# current_monitor_v1-1.net
KiCad netlist of a schematic drawn in EAGLE
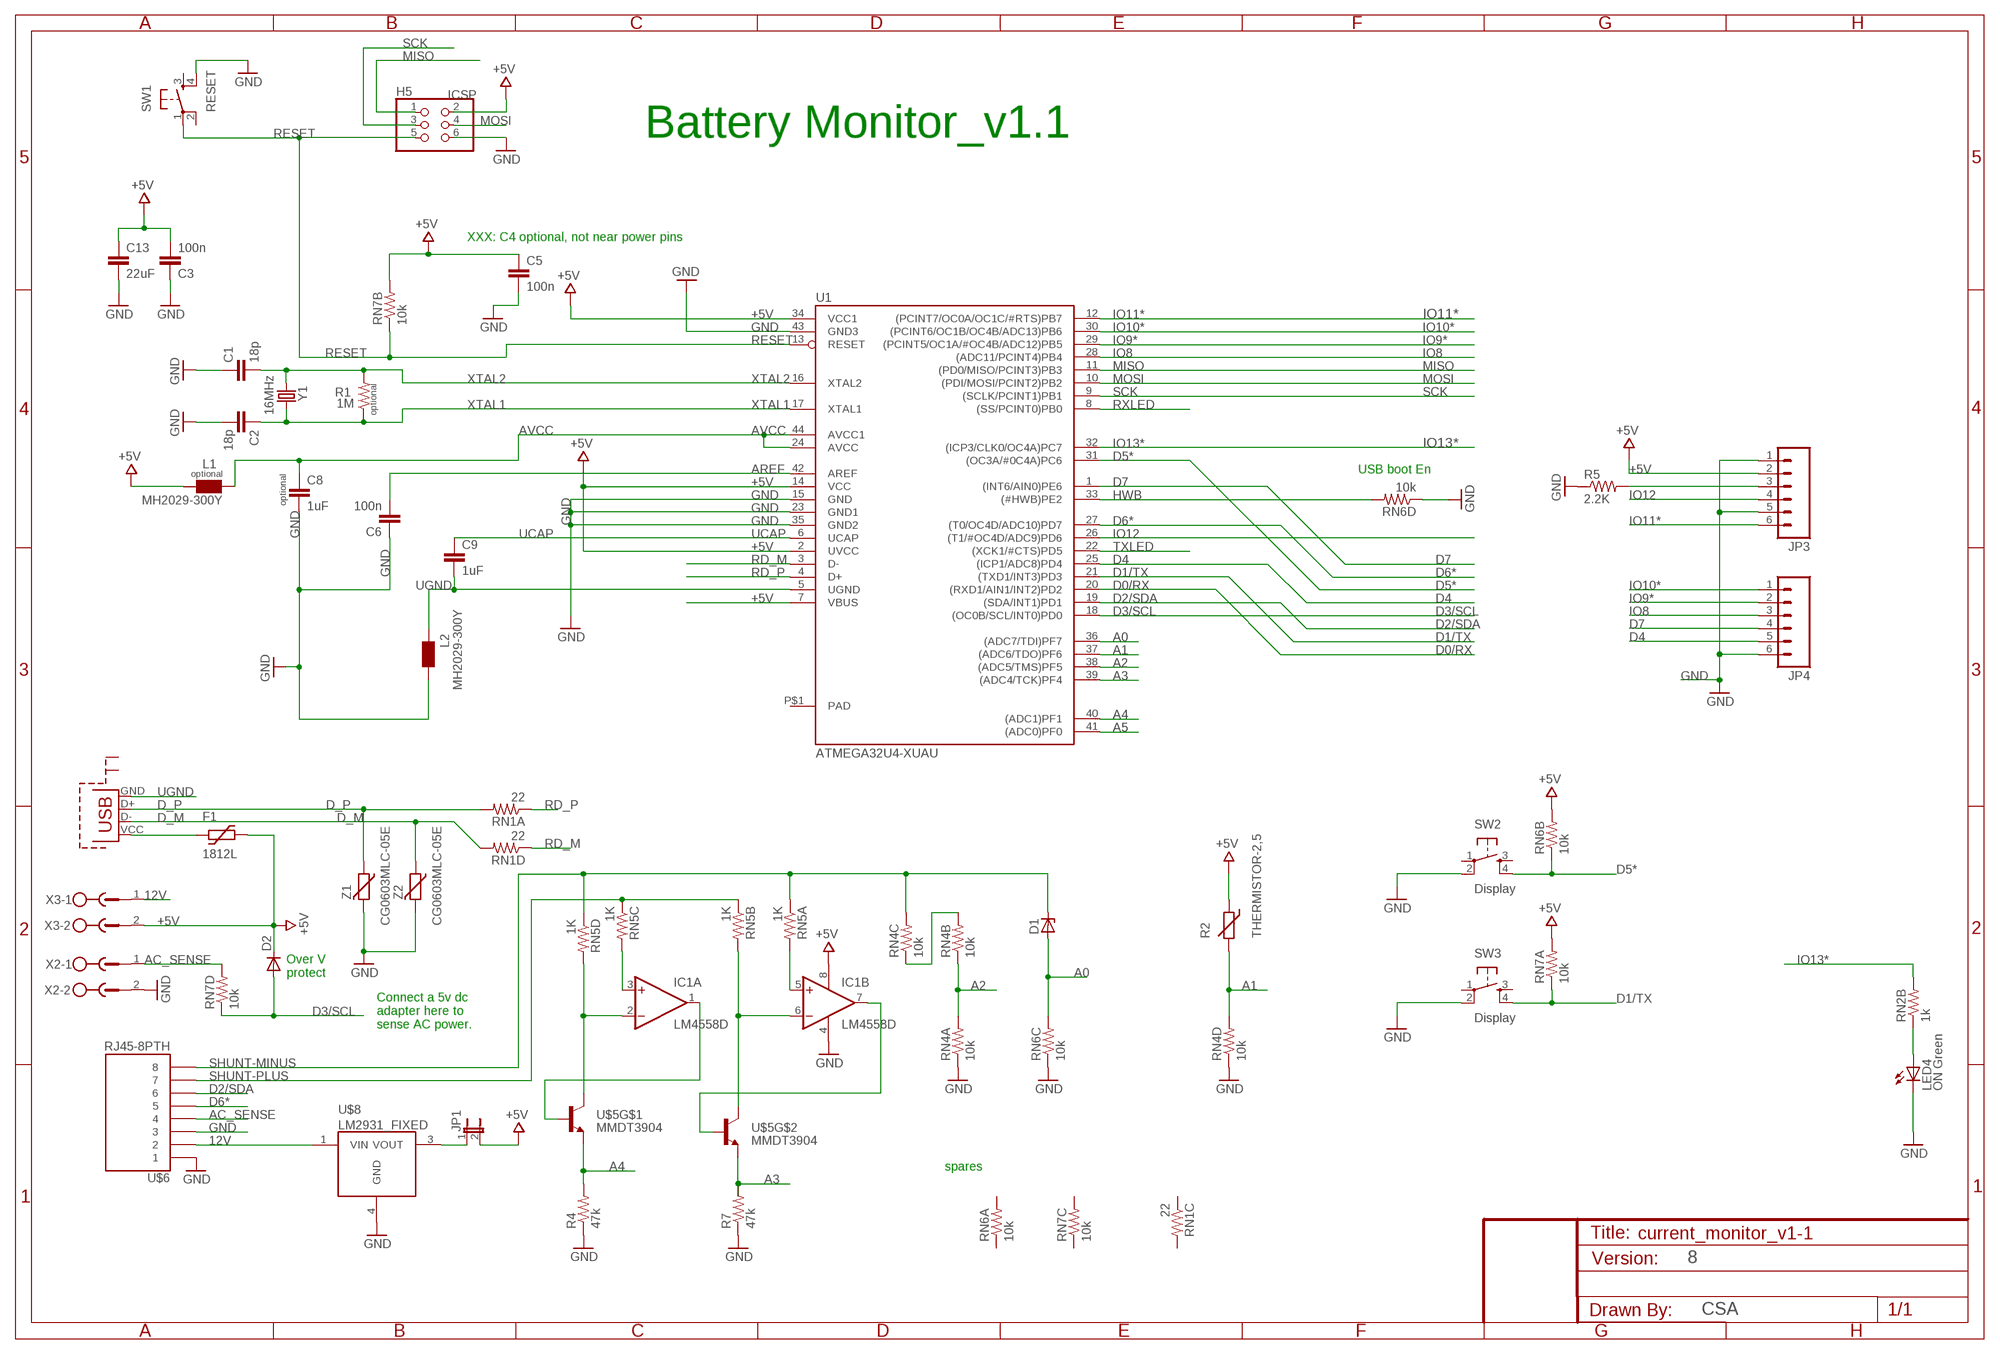
[diagram p0: schematic, sheet 1]

(export (version "E")
  (design (tool "Eeschema 10.0.6"))
  (components
    (comp (ref "C1")
      (value "18p")
      (footprint "eagle-import:0805")
      (libsource (lib "eagle-import") (part "CAP0805"))
    )
    (comp (ref "C2")
      (value "18p")
      (footprint "eagle-import:0805")
      (libsource (lib "eagle-import") (part "CAP0805"))
    )
    (comp (ref "C3")
      (value "100n")
      (footprint "eagle-import:0805")
      (libsource (lib "eagle-import") (part "CAP0805"))
    )
    (comp (ref "C5")
      (value "100n")
      (footprint "eagle-import:0805")
      (libsource (lib "eagle-import") (part "CAP0805"))
    )
    (comp (ref "C6")
      (value "100n")
      (footprint "eagle-import:0805")
      (libsource (lib "eagle-import") (part "CAP0805"))
    )
    (comp (ref "C8")
      (value "1uF")
      (footprint "eagle-import:0805")
      (libsource (lib "eagle-import") (part "CAP0805"))
    )
    (comp (ref "C9")
      (value "1uF")
      (footprint "eagle-import:0805")
      (libsource (lib "eagle-import") (part "CAP0805"))
    )
    (comp (ref "C13")
      (value "22uF")
      (footprint "eagle-import:1206")
      (libsource (lib "eagle-import") (part "CAP1206"))
    )
    (comp (ref "D1")
      (value "ZENER-DIODEZD-5")
      (footprint "eagle-import:ZDIO-5")
      (libsource (lib "eagle-import") (part "ZENER-DIODEZD-5"))
    )
    (comp (ref "D2")
      (value "DIODESMA")
      (footprint "eagle-import:SMA-DIODE")
      (libsource (lib "eagle-import") (part "DIODESMA"))
    )
    (comp (ref "F1")
      (value "1812L")
      (footprint "eagle-import:1812L")
      (libsource (lib "eagle-import") (part "1812L"))
    )
    (comp (ref "H5")
      (value "ICSP")
      (footprint "eagle-import:2X03")
      (libsource (lib "eagle-import") (part "PINHD-2X3"))
    )
    (comp (ref "IC1")
      (value "LM4558D")
      (footprint "eagle-import:SO08")
      (libsource (lib "eagle-import") (part "4558DLM"))
    )
    (comp (ref "JP1")
      (value "JUMPER-2-OLDPTH_LOCK")
      (footprint "eagle-import:1X02_LOCK")
      (libsource (lib "eagle-import") (part "JUMPER-2-OLDPTH_LOCK"))
    )
    (comp (ref "JP3")
      (value "M06FEMALE_LOCK")
      (footprint "eagle-import:1X06_FEMALE_LOCK.010")
      (libsource (lib "eagle-import") (part "M06FEMALE_LOCK"))
    )
    (comp (ref "JP4")
      (value "M06FEMALE_LOCK")
      (footprint "eagle-import:1X06_FEMALE_LOCK.010")
      (libsource (lib "eagle-import") (part "M06FEMALE_LOCK"))
    )
    (comp (ref "L1")
      (value "MH2029-300Y")
      (footprint "eagle-import:0805")
      (libsource (lib "eagle-import") (part "WE-CBF_0805"))
    )
    (comp (ref "L2")
      (value "MH2029-300Y")
      (footprint "eagle-import:0805")
      (libsource (lib "eagle-import") (part "WE-CBF_0805"))
    )
    (comp (ref "LED4")
      (value "ON Green")
      (footprint "eagle-import:LED0805")
      (libsource (lib "eagle-import") (part "LED0805"))
    )
    (comp (ref "R1")
      (value "1M")
      (footprint "eagle-import:0805")
      (libsource (lib "eagle-import") (part "RESISTOR0805-RES"))
    )
    (comp (ref "R2")
      (value "THERMISTOR-2,5")
      (footprint "eagle-import:RS-2,5")
      (libsource (lib "eagle-import") (part "THERMISTOR-2,5"))
    )
    (comp (ref "R4")
      (value "47k")
      (footprint "eagle-import:0805")
      (libsource (lib "eagle-import") (part "RESISTOR0805-RES"))
    )
    (comp (ref "R5")
      (value "2.2K")
      (footprint "eagle-import:0805")
      (libsource (lib "eagle-import") (part "RESISTOR0805-RES"))
    )
    (comp (ref "R7")
      (value "47k")
      (footprint "eagle-import:0805")
      (libsource (lib "eagle-import") (part "RESISTOR0805-RES"))
    )
    (comp (ref "RN1")
      (value "22")
      (footprint "eagle-import:CRA06S")
      (libsource (lib "eagle-import") (part "RESISTOR-ARRAYCRA06S"))
    )
    (comp (ref "RN2")
      (value "1k")
      (footprint "eagle-import:CRA06S")
      (libsource (lib "eagle-import") (part "RESISTOR-ARRAYCRA06S"))
    )
    (comp (ref "RN4")
      (value "10k")
      (footprint "eagle-import:CRA06S")
      (libsource (lib "eagle-import") (part "RESISTOR-ARRAYCRA06S"))
    )
    (comp (ref "RN5")
      (value "1K")
      (footprint "eagle-import:CRA06S")
      (libsource (lib "eagle-import") (part "RESISTOR-ARRAYCRA06S"))
    )
    (comp (ref "RN6")
      (value "10k")
      (footprint "eagle-import:CRA06S")
      (libsource (lib "eagle-import") (part "RESISTOR-ARRAYCRA06S"))
    )
    (comp (ref "RN7")
      (value "10k")
      (footprint "eagle-import:CRA06S")
      (libsource (lib "eagle-import") (part "RESISTOR-ARRAYCRA06S"))
    )
    (comp (ref "SW1")
      (value "RESET")
      (footprint "eagle-import:TACTILE-PTH")
      (libsource (lib "eagle-import") (part "TAC_SWITCHPTH"))
    )
    (comp (ref "SW2")
      (value "Display")
      (footprint "eagle-import:TACTILE-PTH")
      (libsource (lib "eagle-import") (part "TAC_SWITCHPTH"))
    )
    (comp (ref "SW3")
      (value "Display")
      (footprint "eagle-import:TACTILE-PTH")
      (libsource (lib "eagle-import") (part "TAC_SWITCHPTH"))
    )
    (comp (ref "U$5")
      (value "MMDT3904")
      (footprint "eagle-import:SOT363")
      (libsource (lib "eagle-import") (part "MMDT3904"))
    )
    (comp (ref "U$6")
      (value "RJ45-8PTH")
      (footprint "eagle-import:RJ45-8")
      (libsource (lib "eagle-import") (part "RJ45-8PTH"))
    )
    (comp (ref "U$8")
      (value "LM2931_FIXED")
      (footprint "eagle-import:DPAK")
      (libsource (lib "eagle-import") (part "LM2931_FIXED"))
    )
    (comp (ref "U$12")
      (value "USB-MICRO-B-EVT")
      (footprint "eagle-import:USB-MICRO-B-UNIVERSAL-SOLID-FOOTS")
      (libsource (lib "eagle-import") (part "USB-MICRO-B-EVT"))
    )
    (comp (ref "U1")
      (value "ATMEGA32U4-XUAU")
      (footprint "eagle-import:TQFP44-PAD")
      (libsource (lib "eagle-import") (part "ATMEGA32U4-XUAU"))
    )
    (comp (ref "X2")
      (value "MSTBV2")
      (footprint "eagle-import:MSTBV2")
      (libsource (lib "eagle-import") (part "MSTBV2"))
    )
    (comp (ref "X3")
      (value "MSTBV2")
      (footprint "eagle-import:MSTBV2")
      (libsource (lib "eagle-import") (part "MSTBV2"))
    )
    (comp (ref "Y1")
      (value "16MHz")
      (footprint "eagle-import:HC49US")
      (libsource (lib "eagle-import") (part "CRYSTALHC49US"))
    )
    (comp (ref "Z1")
      (value "CG0603MLC-05E")
      (footprint "eagle-import:CT_CN0603")
      (libsource (lib "eagle-import") (part "VARISTORCN0603"))
    )
    (comp (ref "Z2")
      (value "CG0603MLC-05E")
      (footprint "eagle-import:CT_CN0603")
      (libsource (lib "eagle-import") (part "VARISTORCN0603"))
    )
  )
  (nets
    (net (code "1") (name "+5V") (class "Default")
      (node (ref "C13") (pin "1") (pinfunction "1_1") (pintype "passive"))
      (node (ref "C3") (pin "2") (pinfunction "2_2") (pintype "passive"))
      (node (ref "C5") (pin "1") (pinfunction "1_1") (pintype "passive"))
      (node (ref "D2") (pin "C") (pinfunction "C_C") (pintype "passive"))
      (node (ref "F1") (pin "P$2") (pinfunction "2_P$2") (pintype "passive"))
      (node (ref "H5") (pin "2") (pinfunction "2_2") (pintype "passive"))
      (node (ref "IC1") (pin "8") (pinfunction "V+_8") (pintype "power_in"))
      (node (ref "JP1") (pin "2") (pinfunction "2_2") (pintype "passive"))
      (node (ref "JP3") (pin "2") (pinfunction "2_2") (pintype "passive"))
      (node (ref "L1") (pin "1") (pinfunction "1_1") (pintype "passive"))
      (node (ref "R2") (pin "1") (pinfunction "1_1") (pintype "passive"))
      (node (ref "RN6") (pin "7") (pinfunction "2_7") (pintype "passive"))
      (node (ref "RN7") (pin "7") (pinfunction "2_7") (pintype "passive"))
      (node (ref "RN7") (pin "8") (pinfunction "2_8") (pintype "passive"))
      (node (ref "U1") (pin "14") (pinfunction "VCC_14") (pintype "power_in"))
      (node (ref "U1") (pin "2") (pinfunction "UVCC_2") (pintype "power_in"))
      (node (ref "U1") (pin "34") (pinfunction "VCC1_34") (pintype "power_in"))
      (node (ref "U1") (pin "7") (pinfunction "VBUS_7") (pintype "input"))
      (node (ref "X3") (pin "2") (pinfunction "SK_2") (pintype "passive"))
    )
    (net (code "2") (name "/12V") (class "Default")
      (node (ref "U$6") (pin "2") (pinfunction "2_2") (pintype "bidirectional"))
      (node (ref "U$8") (pin "1") (pinfunction "VIN_1") (pintype "bidirectional"))
      (node (ref "X3") (pin "1") (pinfunction "SK_1") (pintype "passive"))
    )
    (net (code "3") (name "/A0") (class "Default")
      (node (ref "D1") (pin "A") (pinfunction "A_A") (pintype "passive"))
      (node (ref "RN6") (pin "6") (pinfunction "2_6") (pintype "passive"))
      (node (ref "U1") (pin "36") (pinfunction "(ADC7/TDI)PF7_36") (pintype "bidirectional"))
    )
    (net (code "4") (name "/A1") (class "Default")
      (node (ref "R2") (pin "2") (pinfunction "2_2") (pintype "passive"))
      (node (ref "RN4") (pin "5") (pinfunction "2_5") (pintype "passive"))
      (node (ref "U1") (pin "37") (pinfunction "(ADC6/TDO)PF6_37") (pintype "bidirectional"))
    )
    (net (code "5") (name "/A2") (class "Default")
      (node (ref "RN4") (pin "2") (pinfunction "1_2") (pintype "passive"))
      (node (ref "RN4") (pin "8") (pinfunction "2_8") (pintype "passive"))
      (node (ref "U1") (pin "38") (pinfunction "(ADC5/TMS)PF5_38") (pintype "bidirectional"))
    )
    (net (code "6") (name "/A3") (class "Default")
      (node (ref "R7") (pin "2") (pinfunction "2_2") (pintype "passive"))
      (node (ref "U$5") (pin "1") (pinfunction "E_1") (pintype "passive"))
      (node (ref "U1") (pin "39") (pinfunction "(ADC4/TCK)PF4_39") (pintype "bidirectional"))
    )
    (net (code "7") (name "/A4") (class "Default")
      (node (ref "R4") (pin "2") (pinfunction "2_2") (pintype "passive"))
      (node (ref "U$5") (pin "4") (pinfunction "E_4") (pintype "passive"))
      (node (ref "U1") (pin "40") (pinfunction "(ADC1)PF1_40") (pintype "bidirectional"))
    )
    (net (code "8") (name "/A5") (class "Default")
      (node (ref "U1") (pin "41") (pinfunction "(ADC0)PF0_41") (pintype "bidirectional"))
    )
    (net (code "9") (name "/AC_SENSE") (class "Default")
      (node (ref "RN7") (pin "5") (pinfunction "2_5") (pintype "passive"))
      (node (ref "U$6") (pin "4") (pinfunction "4_4") (pintype "bidirectional"))
      (node (ref "X2") (pin "1") (pinfunction "SK_1") (pintype "passive"))
    )
    (net (code "10") (name "/AREF") (class "Default")
      (node (ref "C6") (pin "2") (pinfunction "2_2") (pintype "passive"))
      (node (ref "U1") (pin "42") (pinfunction "AREF_42") (pintype "power_in"))
    )
    (net (code "11") (name "/AVCC") (class "Default")
      (node (ref "C8") (pin "1") (pinfunction "1_1") (pintype "passive"))
      (node (ref "L1") (pin "2") (pinfunction "2_2") (pintype "passive"))
      (node (ref "U1") (pin "24") (pinfunction "AVCC_24") (pintype "power_in"))
      (node (ref "U1") (pin "44") (pinfunction "AVCC1_44") (pintype "power_in"))
    )
    (net (code "12") (name "/D0{slash}RX") (class "Default")
      (node (ref "U1") (pin "20") (pinfunction "(RXD1/AIN1/INT2)PD2_20") (pintype "bidirectional"))
    )
    (net (code "13") (name "/D1{slash}TX") (class "Default")
      (node (ref "RN7") (pin "1") (pinfunction "1_1") (pintype "passive"))
      (node (ref "SW3") (pin "4") (pinfunction "4_4") (pintype "passive"))
      (node (ref "U1") (pin "21") (pinfunction "(TXD1/INT3)PD3_21") (pintype "bidirectional"))
    )
    (net (code "14") (name "/D2{slash}SDA") (class "Default")
      (node (ref "U$6") (pin "6") (pinfunction "6_6") (pintype "bidirectional"))
      (node (ref "U1") (pin "19") (pinfunction "(SDA/INT1)PD1_19") (pintype "bidirectional"))
    )
    (net (code "15") (name "/D3{slash}SCL") (class "Default")
      (node (ref "D2") (pin "A") (pinfunction "A_A") (pintype "passive"))
      (node (ref "RN7") (pin "4") (pinfunction "1_4") (pintype "passive"))
      (node (ref "U1") (pin "18") (pinfunction "(OC0B/SCL/INT0)PD0_18") (pintype "bidirectional"))
    )
    (net (code "16") (name "/D4") (class "Default")
      (node (ref "JP4") (pin "5") (pinfunction "5_5") (pintype "passive"))
      (node (ref "U1") (pin "25") (pinfunction "(ICP1/ADC8)PD4_25") (pintype "bidirectional"))
    )
    (net (code "17") (name "/D5*") (class "Default")
      (node (ref "RN6") (pin "2") (pinfunction "1_2") (pintype "passive"))
      (node (ref "SW2") (pin "4") (pinfunction "4_4") (pintype "passive"))
      (node (ref "U1") (pin "31") (pinfunction "(OC3A/#0C4A)PC6_31") (pintype "bidirectional"))
    )
    (net (code "18") (name "/D6*") (class "Default")
      (node (ref "U$6") (pin "5") (pinfunction "5_5") (pintype "bidirectional"))
      (node (ref "U1") (pin "27") (pinfunction "(T0/OC4D/ADC10)PD7_27") (pintype "bidirectional"))
    )
    (net (code "19") (name "/D7") (class "Default")
      (node (ref "JP4") (pin "4") (pinfunction "4_4") (pintype "passive"))
      (node (ref "U1") (pin "1") (pinfunction "(INT6/AIN0)PE6_1") (pintype "bidirectional"))
    )
    (net (code "20") (name "/D_M") (class "Default")
      (node (ref "RN1") (pin "5") (pinfunction "2_5") (pintype "passive"))
      (node (ref "U$12") (pin "D-") (pinfunction "D-_D-") (pintype "bidirectional"))
      (node (ref "Z2") (pin "1") (pinfunction "1_1") (pintype "passive"))
    )
    (net (code "21") (name "/D_P") (class "Default")
      (node (ref "RN1") (pin "8") (pinfunction "2_8") (pintype "passive"))
      (node (ref "U$12") (pin "D+") (pinfunction "D+_D+") (pintype "bidirectional"))
      (node (ref "Z1") (pin "1") (pinfunction "1_1") (pintype "passive"))
    )
    (net (code "22") (name "/HWB") (class "Default")
      (node (ref "RN6") (pin "5") (pinfunction "2_5") (pintype "passive"))
      (node (ref "U1") (pin "33") (pinfunction "(#HWB)PE2_33") (pintype "bidirectional"))
    )
    (net (code "23") (name "/IO8") (class "Default")
      (node (ref "JP4") (pin "3") (pinfunction "3_3") (pintype "passive"))
      (node (ref "U1") (pin "28") (pinfunction "(ADC11/PCINT4)PB4_28") (pintype "bidirectional"))
    )
    (net (code "24") (name "/IO9*") (class "Default")
      (node (ref "JP4") (pin "2") (pinfunction "2_2") (pintype "passive"))
      (node (ref "U1") (pin "29") (pinfunction "(PCINT5/OC1A/#OC4B/ADC12)PB5_29") (pintype "bidirectional"))
    )
    (net (code "25") (name "/IO10*") (class "Default")
      (node (ref "JP4") (pin "1") (pinfunction "1_1") (pintype "passive"))
      (node (ref "U1") (pin "30") (pinfunction "(PCINT6/OC1B/OC4B/ADC13)PB6_30") (pintype "bidirectional"))
    )
    (net (code "26") (name "/IO11*") (class "Default")
      (node (ref "JP3") (pin "6") (pinfunction "6_6") (pintype "passive"))
      (node (ref "U1") (pin "12") (pinfunction "(PCINT7/OC0A/OC1C/#RTS)PB7_12") (pintype "bidirectional"))
    )
    (net (code "27") (name "/IO12") (class "Default")
      (node (ref "JP3") (pin "4") (pinfunction "4_4") (pintype "passive"))
      (node (ref "U1") (pin "26") (pinfunction "(T1/#OC4D/ADC9)PD6_26") (pintype "bidirectional"))
    )
    (net (code "28") (name "/IO13*") (class "Default")
      (node (ref "RN2") (pin "7") (pinfunction "2_7") (pintype "passive"))
      (node (ref "U1") (pin "32") (pinfunction "(ICP3/CLK0/OC4A)PC7_32") (pintype "bidirectional"))
    )
    (net (code "29") (name "/MISO") (class "Default")
      (node (ref "H5") (pin "1") (pinfunction "1_1") (pintype "passive"))
      (node (ref "U1") (pin "11") (pinfunction "(PD0/MISO/PCINT3)PB3_11") (pintype "bidirectional"))
    )
    (net (code "30") (name "/MOSI") (class "Default")
      (node (ref "H5") (pin "4") (pinfunction "4_4") (pintype "passive"))
      (node (ref "U1") (pin "10") (pinfunction "(PDI/MOSI/PCINT2)PB2_10") (pintype "bidirectional"))
    )
    (net (code "31") (name "/PAD") (class "Default")
      (node (ref "U1") (pin "P$1") (pinfunction "PAD_P$1") (pintype "power_in"))
    )
    (net (code "32") (name "/RD_M") (class "Default")
      (node (ref "RN1") (pin "4") (pinfunction "1_4") (pintype "passive"))
      (node (ref "U1") (pin "3") (pinfunction "D-_3") (pintype "bidirectional"))
    )
    (net (code "33") (name "/RD_P") (class "Default")
      (node (ref "RN1") (pin "1") (pinfunction "1_1") (pintype "passive"))
      (node (ref "U1") (pin "4") (pinfunction "D+_4") (pintype "bidirectional"))
    )
    (net (code "34") (name "/RESET") (class "Default")
      (node (ref "H5") (pin "5") (pinfunction "5_5") (pintype "passive"))
      (node (ref "RN7") (pin "2") (pinfunction "1_2") (pintype "passive"))
      (node (ref "SW1") (pin "1") (pinfunction "1_1") (pintype "passive"))
      (node (ref "U1") (pin "13") (pinfunction "RESET_13") (pintype "input"))
    )
    (net (code "35") (name "/RXLED") (class "Default")
      (node (ref "U1") (pin "8") (pinfunction "(SS/PCINT0)PB0_8") (pintype "bidirectional"))
    )
    (net (code "36") (name "/SCK") (class "Default")
      (node (ref "H5") (pin "3") (pinfunction "3_3") (pintype "passive"))
      (node (ref "U1") (pin "9") (pinfunction "(SCLK/PCINT1)PB1_9") (pintype "bidirectional"))
    )
    (net (code "37") (name "/SHUNT-MINUS") (class "Default")
      (node (ref "D1") (pin "C") (pinfunction "C_C") (pintype "passive"))
      (node (ref "RN4") (pin "6") (pinfunction "2_6") (pintype "passive"))
      (node (ref "RN5") (pin "1") (pinfunction "1_1") (pintype "passive"))
      (node (ref "RN5") (pin "4") (pinfunction "1_4") (pintype "passive"))
      (node (ref "U$6") (pin "8") (pinfunction "8_8") (pintype "bidirectional"))
    )
    (net (code "38") (name "/SHUNT-PLUS") (class "Default")
      (node (ref "RN5") (pin "2") (pinfunction "1_2") (pintype "passive"))
      (node (ref "RN5") (pin "3") (pinfunction "1_3") (pintype "passive"))
      (node (ref "U$6") (pin "7") (pinfunction "7_7") (pintype "bidirectional"))
    )
    (net (code "39") (name "/TXLED") (class "Default")
      (node (ref "U1") (pin "22") (pinfunction "(XCK1/#CTS)PD5_22") (pintype "bidirectional"))
    )
    (net (code "40") (name "/UCAP") (class "Default")
      (node (ref "C9") (pin "1") (pinfunction "1_1") (pintype "passive"))
      (node (ref "U1") (pin "6") (pinfunction "UCAP_6") (pintype "passive"))
    )
    (net (code "41") (name "/UGND") (class "Default")
      (node (ref "C9") (pin "2") (pinfunction "2_2") (pintype "passive"))
      (node (ref "L2") (pin "1") (pinfunction "1_1") (pintype "passive"))
      (node (ref "U$12") (pin "GND") (pinfunction "GND_GND") (pintype "bidirectional"))
      (node (ref "U1") (pin "5") (pinfunction "UGND_5") (pintype "power_in"))
    )
    (net (code "42") (name "/XTAL1") (class "Default")
      (node (ref "C2") (pin "1") (pinfunction "1_1") (pintype "passive"))
      (node (ref "R1") (pin "1") (pinfunction "1_1") (pintype "passive"))
      (node (ref "U1") (pin "17") (pinfunction "XTAL1_17") (pintype "bidirectional"))
      (node (ref "Y1") (pin "2") (pinfunction "2_2") (pintype "passive"))
    )
    (net (code "43") (name "/XTAL2") (class "Default")
      (node (ref "C1") (pin "2") (pinfunction "2_2") (pintype "passive"))
      (node (ref "R1") (pin "2") (pinfunction "2_2") (pintype "passive"))
      (node (ref "U1") (pin "16") (pinfunction "XTAL2_16") (pintype "bidirectional"))
      (node (ref "Y1") (pin "1") (pinfunction "1_1") (pintype "passive"))
    )
    (net (code "44") (name "GND") (class "Default")
      (node (ref "C1") (pin "1") (pinfunction "1_1") (pintype "passive"))
      (node (ref "C13") (pin "2") (pinfunction "2_2") (pintype "passive"))
      (node (ref "C2") (pin "2") (pinfunction "2_2") (pintype "passive"))
      (node (ref "C3") (pin "1") (pinfunction "1_1") (pintype "passive"))
      (node (ref "C5") (pin "2") (pinfunction "2_2") (pintype "passive"))
      (node (ref "C6") (pin "1") (pinfunction "1_1") (pintype "passive"))
      (node (ref "C8") (pin "2") (pinfunction "2_2") (pintype "passive"))
      (node (ref "H5") (pin "6") (pinfunction "6_6") (pintype "passive"))
      (node (ref "IC1") (pin "4") (pinfunction "V-_4") (pintype "power_in"))
      (node (ref "JP3") (pin "1") (pinfunction "1_1") (pintype "passive"))
      (node (ref "JP3") (pin "5") (pinfunction "5_5") (pintype "passive"))
      (node (ref "JP4") (pin "6") (pinfunction "6_6") (pintype "passive"))
      (node (ref "L2") (pin "2") (pinfunction "2_2") (pintype "passive"))
      (node (ref "LED4") (pin "C") (pinfunction "C_C") (pintype "passive"))
      (node (ref "R4") (pin "1") (pinfunction "1_1") (pintype "passive"))
      (node (ref "R5") (pin "1") (pinfunction "1_1") (pintype "passive"))
      (node (ref "R7") (pin "1") (pinfunction "1_1") (pintype "passive"))
      (node (ref "RN4") (pin "1") (pinfunction "1_1") (pintype "passive"))
      (node (ref "RN4") (pin "4") (pinfunction "1_4") (pintype "passive"))
      (node (ref "RN6") (pin "3") (pinfunction "1_3") (pintype "passive"))
      (node (ref "RN6") (pin "4") (pinfunction "1_4") (pintype "passive"))
      (node (ref "SW1") (pin "4") (pinfunction "4_4") (pintype "passive"))
      (node (ref "SW2") (pin "2") (pinfunction "2_2") (pintype "passive"))
      (node (ref "SW3") (pin "2") (pinfunction "2_2") (pintype "passive"))
      (node (ref "U$6") (pin "1") (pinfunction "1_1") (pintype "bidirectional"))
      (node (ref "U$6") (pin "3") (pinfunction "3_3") (pintype "bidirectional"))
      (node (ref "U$8") (pin "4") (pinfunction "GND_4") (pintype "bidirectional"))
      (node (ref "U1") (pin "15") (pinfunction "GND_15") (pintype "power_in"))
      (node (ref "U1") (pin "23") (pinfunction "GND1_23") (pintype "power_in"))
      (node (ref "U1") (pin "35") (pinfunction "GND2_35") (pintype "power_in"))
      (node (ref "U1") (pin "43") (pinfunction "GND3_43") (pintype "power_in"))
      (node (ref "X2") (pin "2") (pinfunction "SK_2") (pintype "passive"))
      (node (ref "Z1") (pin "2") (pinfunction "2_2") (pintype "passive"))
      (node (ref "Z2") (pin "2") (pinfunction "2_2") (pintype "passive"))
    )
    (net (code "45") (name "Net-(F1-1)") (class "Default")
      (node (ref "F1") (pin "P$1") (pinfunction "1_P$1") (pintype "passive"))
      (node (ref "U$12") (pin "VCC") (pinfunction "VBUS_VCC") (pintype "bidirectional"))
    )
    (net (code "46") (name "Net-(IC1A-+IN)") (class "Default")
      (node (ref "IC1") (pin "3") (pinfunction "+IN_3") (pintype "input"))
      (node (ref "RN5") (pin "6") (pinfunction "2_6") (pintype "passive"))
    )
    (net (code "47") (name "Net-(IC1A--IN)") (class "Default")
      (node (ref "IC1") (pin "2") (pinfunction "-IN_2") (pintype "input"))
      (node (ref "RN5") (pin "5") (pinfunction "2_5") (pintype "passive"))
      (node (ref "U$5") (pin "3") (pinfunction "C_3") (pintype "passive"))
    )
    (net (code "48") (name "Net-(IC1A-OUT)") (class "Default")
      (node (ref "IC1") (pin "1") (pinfunction "OUT_1") (pintype "output"))
      (node (ref "U$5") (pin "5") (pinfunction "B_5") (pintype "passive"))
    )
    (net (code "49") (name "Net-(IC1B-+IN)") (class "Default")
      (node (ref "IC1") (pin "5") (pinfunction "+IN_5") (pintype "input"))
      (node (ref "RN5") (pin "8") (pinfunction "2_8") (pintype "passive"))
    )
    (net (code "50") (name "Net-(IC1B--IN)") (class "Default")
      (node (ref "IC1") (pin "6") (pinfunction "-IN_6") (pintype "input"))
      (node (ref "RN5") (pin "7") (pinfunction "2_7") (pintype "passive"))
      (node (ref "U$5") (pin "6") (pinfunction "C_6") (pintype "passive"))
    )
    (net (code "51") (name "Net-(IC1B-OUT)") (class "Default")
      (node (ref "IC1") (pin "7") (pinfunction "OUT_7") (pintype "output"))
      (node (ref "U$5") (pin "2") (pinfunction "B_2") (pintype "passive"))
    )
    (net (code "52") (name "Net-(JP3-Pad3)") (class "Default")
      (node (ref "JP3") (pin "3") (pinfunction "3_3") (pintype "passive"))
      (node (ref "R5") (pin "2") (pinfunction "2_2") (pintype "passive"))
    )
    (net (code "53") (name "Net-(RN2B-1)") (class "Default")
      (node (ref "LED4") (pin "A") (pinfunction "A_A") (pintype "passive"))
      (node (ref "RN2") (pin "2") (pinfunction "1_2") (pintype "passive"))
    )
    (net (code "54") (name "Net-(RN4B-2)") (class "Default")
      (node (ref "RN4") (pin "3") (pinfunction "1_3") (pintype "passive"))
      (node (ref "RN4") (pin "7") (pinfunction "2_7") (pintype "passive"))
    )
    (net (code "55") (name "Net-(U$8-VOUT)") (class "Default")
      (node (ref "JP1") (pin "1") (pinfunction "1_1") (pintype "passive"))
      (node (ref "U$8") (pin "3") (pinfunction "VOUT_3") (pintype "bidirectional"))
    )
    (net (code "56") (name "unconnected-(RN1C-1-Pad3)") (class "Default")
      (node (ref "RN1") (pin "3") (pinfunction "1_3") (pintype "passive"))
    )
    (net (code "57") (name "unconnected-(RN1C-2-Pad6)") (class "Default")
      (node (ref "RN1") (pin "6") (pinfunction "2_6") (pintype "passive"))
    )
    (net (code "58") (name "unconnected-(RN6-Pad1)") (class "Default")
      (node (ref "RN6") (pin "1") (pinfunction "1_1") (pintype "passive"))
    )
    (net (code "59") (name "unconnected-(RN6A-2-Pad8)") (class "Default")
      (node (ref "RN6") (pin "8") (pinfunction "2_8") (pintype "passive"))
    )
    (net (code "60") (name "unconnected-(RN7C-1-Pad3)") (class "Default")
      (node (ref "RN7") (pin "3") (pinfunction "1_3") (pintype "passive"))
    )
    (net (code "61") (name "unconnected-(RN7C-2-Pad6)") (class "Default")
      (node (ref "RN7") (pin "6") (pinfunction "2_6") (pintype "passive"))
    )
    (net (code "62") (name "unconnected-(SW1-Pad2)") (class "Default")
      (node (ref "SW1") (pin "2") (pinfunction "2_2") (pintype "passive"))
    )
    (net (code "63") (name "unconnected-(SW1-Pad3)") (class "Default")
      (node (ref "SW1") (pin "3") (pinfunction "3_3") (pintype "passive"))
    )
    (net (code "64") (name "unconnected-(SW2-Pad1)") (class "Default")
      (node (ref "SW2") (pin "1") (pinfunction "1_1") (pintype "passive"))
    )
    (net (code "65") (name "unconnected-(SW2-Pad3)") (class "Default")
      (node (ref "SW2") (pin "3") (pinfunction "3_3") (pintype "passive"))
    )
    (net (code "66") (name "unconnected-(SW3-Pad1)") (class "Default")
      (node (ref "SW3") (pin "1") (pinfunction "1_1") (pintype "passive"))
    )
    (net (code "67") (name "unconnected-(SW3-Pad3)") (class "Default")
      (node (ref "SW3") (pin "3") (pinfunction "3_3") (pintype "passive"))
    )
    (net (code "68") (name "unconnected-(U$12-SHIELD1-PadP$4)") (class "Default")
      (node (ref "U$12") (pin "P$4") (pinfunction "SHIELD1_P$4") (pintype "bidirectional"))
    )
    (net (code "69") (name "unconnected-(U$12-SHIELD2-PadP$1)") (class "Default")
      (node (ref "U$12") (pin "P$1") (pinfunction "SHIELD2_P$1") (pintype "bidirectional"))
    )
  )
)
